# zxld383-boost-driver-12mm.net
KiCad netlist of a schematic drawn in EAGLE
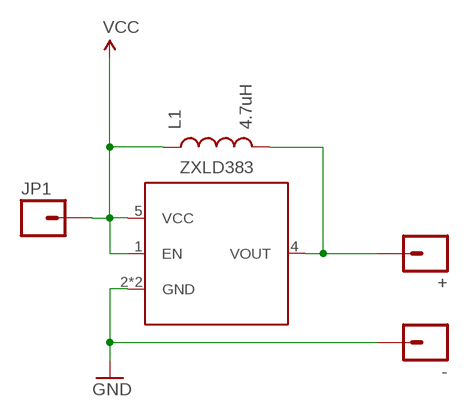
[diagram p0: schematic, sheet 1]

(export (version "E")
  (design (tool "Eeschema 10.0.6"))
  (components
    (comp (ref "+")
      (value "M01PTH-1.2MM")
      (footprint "eagle-import:1X01-1.2MM")
      (libsource (lib "eagle-import") (part "M01PTH-1.2MM"))
    )
    (comp (ref "-")
      (value "M01PTH-1.2MM-NS")
      (footprint "eagle-import:1X01-1.2MM-NS")
      (libsource (lib "eagle-import") (part "M01PTH-1.2MM-NS"))
    )
    (comp (ref "JP1")
      (value "M01NOT-A-VIA-NOPE")
      (footprint "eagle-import:1X01_NOSILK_NOSTOP")
      (libsource (lib "eagle-import") (part "M01NOT-A-VIA-NOPE"))
    )
    (comp (ref "L1")
      (value "4.7uH")
      (footprint "eagle-import:1007")
      (libsource (lib "eagle-import") (part "INDUCTOR1007"))
    )
    (comp (ref "ZXLD383")
      (value "ZXLD383")
      (footprint "eagle-import:TSOT-23-5")
      (libsource (lib "eagle-import") (part "ZXLD383"))
    )
  )
  (nets
    (net (code "1") (name "GND") (class "Default")
      (node (ref "-") (pin "P$1") (pinfunction "1_P$1") (pintype "passive"))
      (node (ref "ZXLD383") (pin "2") (pinfunction "GND_2") (pintype "bidirectional"))
      (node (ref "ZXLD383") (pin "3") (pinfunction "GND_3") (pintype "bidirectional"))
    )
    (net (code "2") (name "Net-(+-1)") (class "Default")
      (node (ref "+") (pin "P$1") (pinfunction "1_P$1") (pintype "passive"))
      (node (ref "L1") (pin "2") (pinfunction "2_2") (pintype "passive"))
      (node (ref "ZXLD383") (pin "4") (pinfunction "VOUT_4") (pintype "bidirectional"))
    )
    (net (code "3") (name "VCC") (class "Default")
      (node (ref "JP1") (pin "P$1") (pinfunction "1_P$1") (pintype "passive"))
      (node (ref "L1") (pin "1") (pinfunction "1_1") (pintype "passive"))
      (node (ref "ZXLD383") (pin "1") (pinfunction "EN_1") (pintype "bidirectional"))
      (node (ref "ZXLD383") (pin "5") (pinfunction "VCC_5") (pintype "bidirectional"))
    )
  )
)
